# smoothieboard-alt-p5.net
KiCad netlist of a schematic drawn in Altium Designer
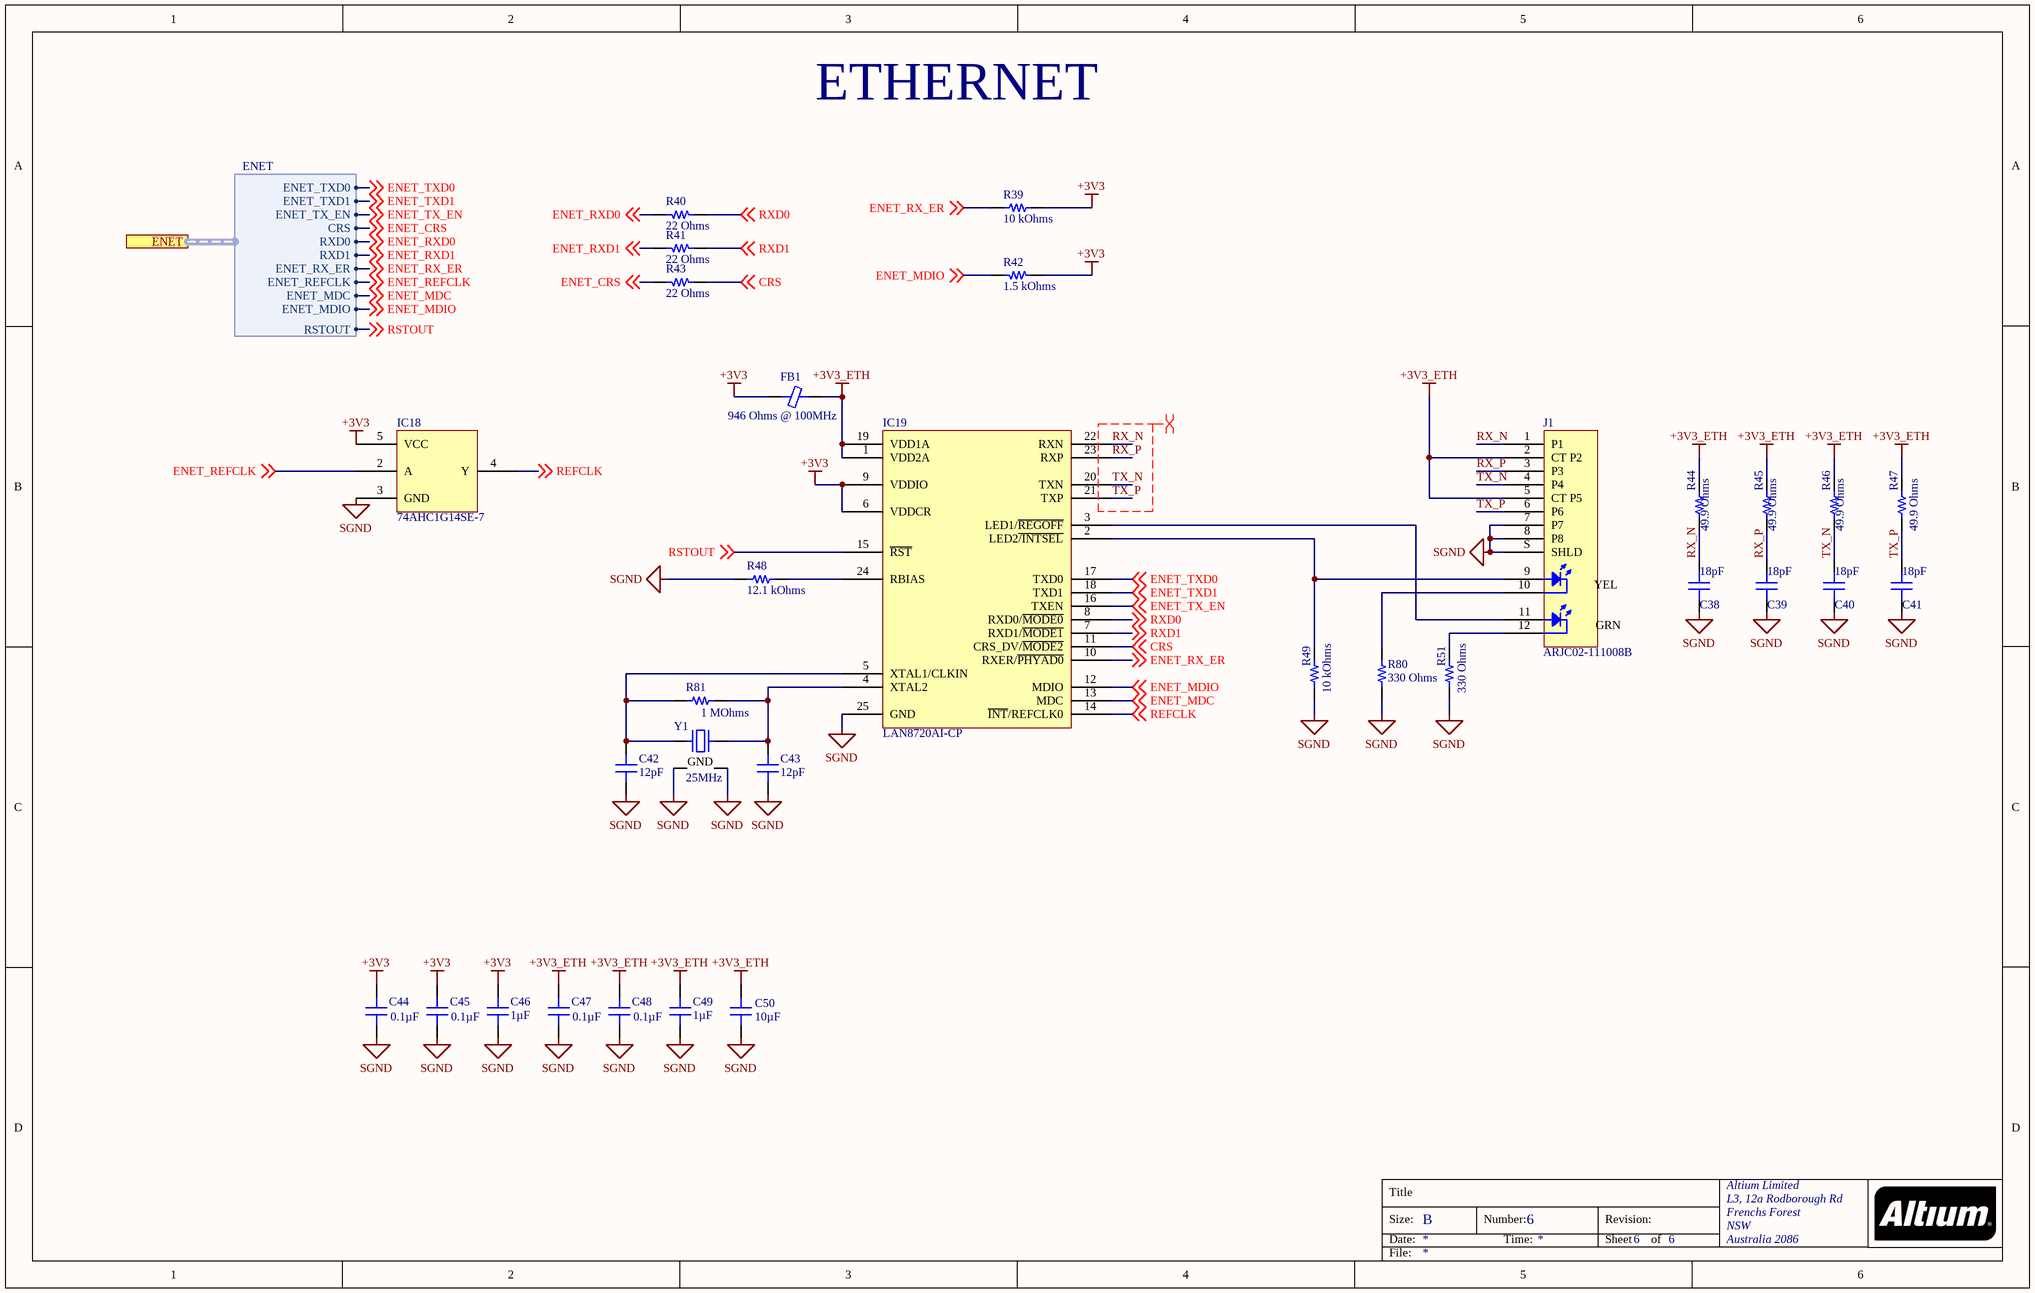
[diagram p0: smoothieboard-alt-p5.SchDoc]

(export (version "E")
  (design (tool "Eeschema 10.0.6"))
  (components
    (comp (ref "C38")
      (value "18pF")
      (footprint "CAP 0402_1005")
      (description "CAP CER 18PF 16V C0G/NP0 0402")
      (fields
        (field (name "PART NUMBER") "VJ0402A180JXJPW1BC")
        (field (name "MANUFACTURER") "Vishay Vitramon")
      )
      (libsource (lib "CAL") (part "Capacitor"))
    )
    (comp (ref "C39")
      (value "18pF")
      (footprint "CAP 0402_1005")
      (description "CAP CER 18PF 16V C0G/NP0 0402")
      (fields
        (field (name "PART NUMBER") "VJ0402A180JXJPW1BC")
        (field (name "MANUFACTURER") "Vishay Vitramon")
      )
      (libsource (lib "CAL") (part "Capacitor"))
    )
    (comp (ref "C40")
      (value "18pF")
      (footprint "CAP 0402_1005")
      (description "CAP CER 18PF 16V C0G/NP0 0402")
      (fields
        (field (name "PART NUMBER") "VJ0402A180JXJPW1BC")
        (field (name "MANUFACTURER") "Vishay Vitramon")
      )
      (libsource (lib "CAL") (part "Capacitor"))
    )
    (comp (ref "C41")
      (value "18pF")
      (footprint "CAP 0402_1005")
      (description "CAP CER 18PF 16V C0G/NP0 0402")
      (fields
        (field (name "PART NUMBER") "VJ0402A180JXJPW1BC")
        (field (name "MANUFACTURER") "Vishay Vitramon")
      )
      (libsource (lib "CAL") (part "Capacitor"))
    )
    (comp (ref "C42")
      (value "12pF")
      (footprint "CAP 0402_1005")
      (description "CAP CER 12PF 10V NP0 0402")
      (fields (field (name "PART NUMBER") "C0402C120J8GAC7867") (field (name "MANUFACTURER") "KEMET"))
      (libsource (lib "CAL") (part "Capacitor"))
    )
    (comp (ref "C43")
      (value "12pF")
      (footprint "CAP 0402_1005")
      (description "CAP CER 12PF 10V NP0 0402")
      (fields (field (name "PART NUMBER") "C0402C120J8GAC7867") (field (name "MANUFACTURER") "KEMET"))
      (libsource (lib "CAL") (part "Capacitor"))
    )
    (comp (ref "C44")
      (value "0.1µF")
      (footprint "CAP 0402_1005")
      (description "CAP CER 0.1UF 6.3V X5R 0402")
      (fields (field (name "PART NUMBER") "CC0402MRX5R5BB104") (field (name "MANUFACTURER") "Yageo"))
      (libsource (lib "CAL") (part "Capacitor"))
    )
    (comp (ref "C45")
      (value "0.1µF")
      (footprint "CAP 0402_1005")
      (description "CAP CER 0.1UF 6.3V X5R 0402")
      (fields (field (name "PART NUMBER") "CC0402MRX5R5BB104") (field (name "MANUFACTURER") "Yageo"))
      (libsource (lib "CAL") (part "Capacitor"))
    )
    (comp (ref "C46")
      (value "1µF")
      (footprint "CAP 0603_1608")
      (description "CAP CER 1UF 50V X5R 0603")
      (fields (field (name "PART NUMBER") "UMK107ABJ105MAHT") (field (name "MANUFACTURER") "Taiyo Yuden"))
      (libsource (lib "CAL") (part "Capacitor"))
    )
    (comp (ref "C47")
      (value "0.1µF")
      (footprint "CAP 0402_1005")
      (description "CAP CER 0.1UF 6.3V X5R 0402")
      (fields (field (name "PART NUMBER") "CC0402MRX5R5BB104") (field (name "MANUFACTURER") "Yageo"))
      (libsource (lib "CAL") (part "Capacitor"))
    )
    (comp (ref "C48")
      (value "0.1µF")
      (footprint "CAP 0402_1005")
      (description "CAP CER 0.1UF 6.3V X5R 0402")
      (fields (field (name "PART NUMBER") "CC0402MRX5R5BB104") (field (name "MANUFACTURER") "Yageo"))
      (libsource (lib "CAL") (part "Capacitor"))
    )
    (comp (ref "C49")
      (value "1µF")
      (footprint "CAP 0603_1608")
      (description "CAP CER 1UF 50V X5R 0603")
      (fields (field (name "PART NUMBER") "UMK107ABJ105MAHT") (field (name "MANUFACTURER") "Taiyo Yuden"))
      (libsource (lib "CAL") (part "Capacitor"))
    )
    (comp (ref "C50")
      (value "10µF")
      (footprint "CAP 0603_1608")
      (description "CAP CER 10UF 6.3V X5R 0603")
      (fields
        (field (name "PART NUMBER") "GRM188R60J106KE47D")
        (field (name "MANUFACTURER") "Murata Electronics")
      )
      (libsource (lib "CAL") (part "Capacitor"))
    )
    (comp (ref "FB1")
      (value "946 Ohms @ 100MHz")
      (footprint "FER 1206_3216")
      (description "FERRITE BEAD 946 OHM 1206 1LN")
      (fields
        (field (name "PART NUMBER") "LF1206E152R-10")
        (field (name "MANUFACTURER") "Laird-Signal Integrity Products")
      )
      (libsource (lib "CAL") (part "Ferrite Chip"))
    )
    (comp (ref "IC18")
      (value "74AHC1G14SE-7")
      (footprint "DIODES INC - SOT353")
      (description "IC INVERTER SCHMITT 1CH SOT353")
      (fields (field (name "MANUFACTURER") "Diodes Incorporated"))
      (libsource (lib "CAL") (part "DIODES 74AHC1G14SE-7"))
    )
    (comp (ref "IC19")
      (value "LAN8720AI-CP")
      (footprint "SMSC QFN-24 4X4MM")
      (description "IC TRANSCEIVER FULL 2/2 24QFN")
      (fields (field (name "MANUFACTURER") "Microchip Technology"))
      (libsource (lib "CAL") (part "SMSC LAN8720"))
    )
    (comp (ref "J1")
      (value "ARJC02-111008B")
      (footprint "ABRACON ARJC02-111008B")
      (description "CONN MAGJACK 1PORT 100 BASE-TX")
      (fields (field (name "MANUFACTURER") "Abracon LLC"))
      (libsource (lib "CAL") (part "Modular Jack with Magnetics Shield LEDS"))
    )
    (comp (ref "R39")
      (value "10 kOhms")
      (footprint "RES 0603_1608")
      (description "RES SMD 10K OHM 5% 1/4W 0603")
      (fields (field (name "PART NUMBER") "RCS060310K0JNEA") (field (name "MANUFACTURER") "Vishay Dale"))
      (libsource (lib "CAL") (part "Resistor"))
    )
    (comp (ref "R40")
      (value "22 Ohms")
      (footprint "RES 0603_1608")
      (description "RES SMD 22 OHM 1% 1/10W 0603")
      (fields
        (field (name "PART NUMBER") "ERJ-3EKF22R0V")
        (field (name "MANUFACTURER") "Panasonic Electronic Components")
      )
      (libsource (lib "CAL") (part "Resistor"))
    )
    (comp (ref "R41")
      (value "22 Ohms")
      (footprint "RES 0603_1608")
      (description "RES SMD 22 OHM 1% 1/10W 0603")
      (fields
        (field (name "PART NUMBER") "ERJ-3EKF22R0V")
        (field (name "MANUFACTURER") "Panasonic Electronic Components")
      )
      (libsource (lib "CAL") (part "Resistor"))
    )
    (comp (ref "R42")
      (value "1.5 kOhms")
      (footprint "RES 0402_1005")
      (description "RES SMD 1.5K OHM 1% 1/5W 0402")
      (fields (field (name "PART NUMBER") "RCS04021K50FKED") (field (name "MANUFACTURER") "Vishay Dale"))
      (libsource (lib "CAL") (part "Resistor"))
    )
    (comp (ref "R43")
      (value "22 Ohms")
      (footprint "RES 0603_1608")
      (description "RES SMD 22 OHM 1% 1/10W 0603")
      (fields
        (field (name "PART NUMBER") "ERJ-3EKF22R0V")
        (field (name "MANUFACTURER") "Panasonic Electronic Components")
      )
      (libsource (lib "CAL") (part "Resistor"))
    )
    (comp (ref "R44")
      (value "49.9 Ohms")
      (footprint "RES 0402_1005")
      (description "RES SMD 49.9 OHM 0.5% 1/16W 0402")
      (fields (field (name "PART NUMBER") "RR0510R-49R9-D") (field (name "MANUFACTURER") "Susumu"))
      (libsource (lib "CAL") (part "Resistor"))
    )
    (comp (ref "R45")
      (value "49.9 Ohms")
      (footprint "RES 0402_1005")
      (description "RES SMD 49.9 OHM 0.5% 1/16W 0402")
      (fields (field (name "PART NUMBER") "RR0510R-49R9-D") (field (name "MANUFACTURER") "Susumu"))
      (libsource (lib "CAL") (part "Resistor"))
    )
    (comp (ref "R46")
      (value "49.9 Ohms")
      (footprint "RES 0402_1005")
      (description "RES SMD 49.9 OHM 0.5% 1/16W 0402")
      (fields (field (name "PART NUMBER") "RR0510R-49R9-D") (field (name "MANUFACTURER") "Susumu"))
      (libsource (lib "CAL") (part "Resistor"))
    )
    (comp (ref "R47")
      (value "49.9 Ohms")
      (footprint "RES 0402_1005")
      (description "RES SMD 49.9 OHM 0.5% 1/16W 0402")
      (fields (field (name "PART NUMBER") "RR0510R-49R9-D") (field (name "MANUFACTURER") "Susumu"))
      (libsource (lib "CAL") (part "Resistor"))
    )
    (comp (ref "R48")
      (value "12.1 kOhms")
      (footprint "RES 0402_1005")
      (description "RES SMD 12.1K OHM 1% 1/16W 0402")
      (fields (field (name "PART NUMBER") "CRCW040212K1FKTD") (field (name "MANUFACTURER") "Vishay Dale"))
      (libsource (lib "CAL") (part "Resistor"))
    )
    (comp (ref "R49")
      (value "10 kOhms")
      (footprint "RES 0603_1608")
      (description "RES SMD 10K OHM 5% 1/4W 0603")
      (fields (field (name "PART NUMBER") "RCS060310K0JNEA") (field (name "MANUFACTURER") "Vishay Dale"))
      (libsource (lib "CAL") (part "Resistor"))
    )
    (comp (ref "R51")
      (value "330 Ohms")
      (footprint "RES 0603_1608")
      (description "RES SMD 330 OHM 5% 1/10W 0603")
      (fields
        (field (name "PART NUMBER") "ERJ-3GEYJ331V")
        (field (name "MANUFACTURER") "Panasonic Electronic Components")
      )
      (libsource (lib "CAL") (part "Resistor"))
    )
    (comp (ref "R80")
      (value "330 Ohms")
      (footprint "RES 0603_1608")
      (description "RES SMD 330 OHM 5% 1/10W 0603")
      (fields
        (field (name "PART NUMBER") "ERJ-3GEYJ331V")
        (field (name "MANUFACTURER") "Panasonic Electronic Components")
      )
      (libsource (lib "CAL") (part "Resistor"))
    )
    (comp (ref "R81")
      (value "1 MOhms")
      (footprint "RES 0402_1005")
      (description "RES SMD 1M OHM 1% 1/5W 0402")
      (fields (field (name "PART NUMBER") "RCS04021M00FKED") (field (name "MANUFACTURER") "Vishay Dale"))
      (libsource (lib "CAL") (part "Resistor"))
    )
    (comp (ref "Y1")
      (value "25MHz")
      (footprint "KYOCERA CX2016DB")
      (description "CRYSTAL 25.0000MHZ 12PF SMD")
      (fields
        (field (name "PART NUMBER") "CX2016DB25000H0FLJC1")
        (field (name "MANUFACTURER") "Kyocera International Inc. Electronic Components")
      )
      (libsource (lib "CAL") (part "Kyocera Crystal CX2016DB"))
    )
  )
  (nets
    (net (code "2") (name "+3V3") (class "Default")
      (node (ref "C44") (pin "2") (pinfunction "2_2") (pintype "passive"))
      (node (ref "C45") (pin "2") (pinfunction "2_2") (pintype "passive"))
      (node (ref "C46") (pin "2") (pinfunction "2_2") (pintype "passive"))
      (node (ref "FB1") (pin "1") (pinfunction "1_1") (pintype "passive"))
      (node (ref "IC18") (pin "5") (pinfunction "VCC_5") (pintype "passive"))
      (node (ref "IC19") (pin "6") (pinfunction "VDDCR_6") (pintype "passive"))
      (node (ref "IC19") (pin "9") (pinfunction "VDDIO_9") (pintype "passive"))
      (node (ref "R39") (pin "2") (pinfunction "2_2") (pintype "passive"))
      (node (ref "R42") (pin "1") (pinfunction "1_1") (pintype "passive"))
    )
    (net (code "3") (name "+3V3_ETH") (class "Default")
      (node (ref "C47") (pin "2") (pinfunction "2_2") (pintype "passive"))
      (node (ref "C48") (pin "2") (pinfunction "2_2") (pintype "passive"))
      (node (ref "C49") (pin "2") (pinfunction "2_2") (pintype "passive"))
      (node (ref "C50") (pin "2") (pinfunction "2_2") (pintype "passive"))
      (node (ref "FB1") (pin "2") (pinfunction "2_2") (pintype "passive"))
      (node (ref "IC19") (pin "1") (pinfunction "VDD2A_1") (pintype "passive"))
      (node (ref "IC19") (pin "19") (pinfunction "VDD1A_19") (pintype "passive"))
      (node (ref "J1") (pin "2") (pinfunction "CT_P2_2") (pintype "passive"))
      (node (ref "J1") (pin "5") (pinfunction "CT_P5_5") (pintype "passive"))
      (node (ref "R44") (pin "2") (pinfunction "2_2") (pintype "passive"))
      (node (ref "R45") (pin "2") (pinfunction "2_2") (pintype "passive"))
      (node (ref "R46") (pin "2") (pinfunction "2_2") (pintype "passive"))
      (node (ref "R47") (pin "2") (pinfunction "2_2") (pintype "passive"))
    )
    (net (code "4") (name "/RX_N") (class "Default")
      (node (ref "C38") (pin "2") (pinfunction "2_2") (pintype "passive"))
      (node (ref "IC19") (pin "22") (pinfunction "RXN_22") (pintype "passive"))
      (node (ref "J1") (pin "1") (pinfunction "P1_1") (pintype "passive"))
      (node (ref "R44") (pin "1") (pinfunction "1_1") (pintype "passive"))
    )
    (net (code "5") (name "/RX_P") (class "Default")
      (node (ref "C39") (pin "2") (pinfunction "2_2") (pintype "passive"))
      (node (ref "IC19") (pin "23") (pinfunction "RXP_23") (pintype "passive"))
      (node (ref "J1") (pin "3") (pinfunction "P3_3") (pintype "passive"))
      (node (ref "R45") (pin "1") (pinfunction "1_1") (pintype "passive"))
    )
    (net (code "6") (name "/TX_N") (class "Default")
      (node (ref "C40") (pin "2") (pinfunction "2_2") (pintype "passive"))
      (node (ref "IC19") (pin "20") (pinfunction "TXN_20") (pintype "passive"))
      (node (ref "J1") (pin "4") (pinfunction "P4_4") (pintype "passive"))
      (node (ref "R46") (pin "1") (pinfunction "1_1") (pintype "passive"))
    )
    (net (code "7") (name "/TX_P") (class "Default")
      (node (ref "C41") (pin "2") (pinfunction "2_2") (pintype "passive"))
      (node (ref "IC19") (pin "21") (pinfunction "TXP_21") (pintype "passive"))
      (node (ref "J1") (pin "6") (pinfunction "P6_6") (pintype "passive"))
      (node (ref "R47") (pin "1") (pinfunction "1_1") (pintype "passive"))
    )
    (net (code "9") (name "CRS") (class "Default")
      (node (ref "IC19") (pin "11") (pinfunction "CRS_DV/~{MODE2}_11") (pintype "passive"))
      (node (ref "R43") (pin "1") (pinfunction "1_1") (pintype "passive"))
    )
    (net (code "10") (name "ENET_CRS") (class "Default")
      (node (ref "R43") (pin "2") (pinfunction "2_2") (pintype "passive"))
    )
    (net (code "11") (name "ENET_MDC") (class "Default")
      (node (ref "IC19") (pin "13") (pinfunction "MDC_13") (pintype "passive"))
    )
    (net (code "12") (name "ENET_MDIO") (class "Default")
      (node (ref "IC19") (pin "12") (pinfunction "MDIO_12") (pintype "passive"))
      (node (ref "R42") (pin "2") (pinfunction "2_2") (pintype "passive"))
    )
    (net (code "13") (name "ENET_REFCLK") (class "Default")
      (node (ref "IC18") (pin "2") (pinfunction "A_2") (pintype "passive"))
    )
    (net (code "14") (name "ENET_RXD0") (class "Default")
      (node (ref "R40") (pin "2") (pinfunction "2_2") (pintype "passive"))
    )
    (net (code "15") (name "ENET_RXD1") (class "Default")
      (node (ref "R41") (pin "2") (pinfunction "2_2") (pintype "passive"))
    )
    (net (code "16") (name "ENET_RX_ER") (class "Default")
      (node (ref "IC19") (pin "10") (pinfunction "RXER/~{PHYAD0}_10") (pintype "passive"))
      (node (ref "R39") (pin "1") (pinfunction "1_1") (pintype "passive"))
    )
    (net (code "17") (name "ENET_TXD0") (class "Default")
      (node (ref "IC19") (pin "17") (pinfunction "TXD0_17") (pintype "passive"))
    )
    (net (code "18") (name "ENET_TXD1") (class "Default")
      (node (ref "IC19") (pin "18") (pinfunction "TXD1_18") (pintype "passive"))
    )
    (net (code "19") (name "ENET_TX_EN") (class "Default")
      (node (ref "IC19") (pin "16") (pinfunction "TXEN_16") (pintype "passive"))
    )
    (net (code "20") (name "Net-(IC19-LED1{slash}~{REGOFF})") (class "Default")
      (node (ref "IC19") (pin "3") (pinfunction "LED1/~{REGOFF}_3") (pintype "passive"))
      (node (ref "J1") (pin "11") (pinfunction "P11_11") (pintype "passive"))
    )
    (net (code "21") (name "Net-(IC19-LED2~{{slash}INTSEL})") (class "Default")
      (node (ref "IC19") (pin "2") (pinfunction "LED2~{/INTSEL}_2") (pintype "passive"))
      (node (ref "J1") (pin "9") (pinfunction "P9_9") (pintype "passive"))
      (node (ref "R49") (pin "1") (pinfunction "1_1") (pintype "passive"))
    )
    (net (code "22") (name "Net-(IC19-RBIAS)") (class "Default")
      (node (ref "IC19") (pin "24") (pinfunction "RBIAS_24") (pintype "passive"))
      (node (ref "R48") (pin "2") (pinfunction "2_2") (pintype "passive"))
    )
    (net (code "23") (name "Net-(IC19-XTAL1{slash}CLKIN)") (class "Default")
      (node (ref "C42") (pin "1") (pinfunction "1_1") (pintype "passive"))
      (node (ref "IC19") (pin "5") (pinfunction "XTAL1/CLKIN_5") (pintype "passive"))
      (node (ref "R81") (pin "2") (pinfunction "2_2") (pintype "passive"))
      (node (ref "Y1") (pin "1") (pinfunction "1_1") (pintype "passive"))
    )
    (net (code "24") (name "Net-(IC19-XTAL2)") (class "Default")
      (node (ref "C43") (pin "1") (pinfunction "1_1") (pintype "passive"))
      (node (ref "IC19") (pin "4") (pinfunction "XTAL2_4") (pintype "passive"))
      (node (ref "R81") (pin "1") (pinfunction "1_1") (pintype "passive"))
      (node (ref "Y1") (pin "3") (pinfunction "3_3") (pintype "passive"))
    )
    (net (code "25") (name "Net-(J1-P10)") (class "Default")
      (node (ref "J1") (pin "10") (pinfunction "P10_10") (pintype "passive"))
      (node (ref "R80") (pin "1") (pinfunction "1_1") (pintype "passive"))
    )
    (net (code "26") (name "Net-(J1-P12)") (class "Default")
      (node (ref "J1") (pin "12") (pinfunction "P12_12") (pintype "passive"))
      (node (ref "R51") (pin "1") (pinfunction "1_1") (pintype "passive"))
    )
    (net (code "27") (name "REFCLK") (class "Default")
      (node (ref "IC18") (pin "4") (pinfunction "Y_4") (pintype "passive"))
      (node (ref "IC19") (pin "14") (pinfunction "~{INT}/REFCLK0_14") (pintype "passive"))
    )
    (net (code "28") (name "RSTOUT") (class "Default")
      (node (ref "IC19") (pin "15") (pinfunction "~{RST}_15") (pintype "passive"))
    )
    (net (code "29") (name "RXD0") (class "Default")
      (node (ref "IC19") (pin "8") (pinfunction "RXD0/~{MODE0}_8") (pintype "passive"))
      (node (ref "R40") (pin "1") (pinfunction "1_1") (pintype "passive"))
    )
    (net (code "30") (name "RXD1") (class "Default")
      (node (ref "IC19") (pin "7") (pinfunction "RXD1/~{MODE1}_7") (pintype "passive"))
      (node (ref "R41") (pin "1") (pinfunction "1_1") (pintype "passive"))
    )
    (net (code "31") (name "SGND") (class "Default")
      (node (ref "C38") (pin "1") (pinfunction "1_1") (pintype "passive"))
      (node (ref "C39") (pin "1") (pinfunction "1_1") (pintype "passive"))
      (node (ref "C40") (pin "1") (pinfunction "1_1") (pintype "passive"))
      (node (ref "C41") (pin "1") (pinfunction "1_1") (pintype "passive"))
      (node (ref "C42") (pin "2") (pinfunction "2_2") (pintype "passive"))
      (node (ref "C43") (pin "2") (pinfunction "2_2") (pintype "passive"))
      (node (ref "C44") (pin "1") (pinfunction "1_1") (pintype "passive"))
      (node (ref "C45") (pin "1") (pinfunction "1_1") (pintype "passive"))
      (node (ref "C46") (pin "1") (pinfunction "1_1") (pintype "passive"))
      (node (ref "C47") (pin "1") (pinfunction "1_1") (pintype "passive"))
      (node (ref "C48") (pin "1") (pinfunction "1_1") (pintype "passive"))
      (node (ref "C49") (pin "1") (pinfunction "1_1") (pintype "passive"))
      (node (ref "C50") (pin "1") (pinfunction "1_1") (pintype "passive"))
      (node (ref "IC18") (pin "3") (pinfunction "GND_3") (pintype "passive"))
      (node (ref "IC19") (pin "25") (pinfunction "GND_25") (pintype "passive"))
      (node (ref "J1") (pin "7") (pinfunction "P7_7") (pintype "passive"))
      (node (ref "J1") (pin "8") (pinfunction "P8_8") (pintype "passive"))
      (node (ref "J1") (pin "S") (pinfunction "SHLD_S") (pintype "passive"))
      (node (ref "R48") (pin "1") (pinfunction "1_1") (pintype "passive"))
      (node (ref "R49") (pin "2") (pinfunction "2_2") (pintype "passive"))
      (node (ref "R51") (pin "2") (pinfunction "2_2") (pintype "passive"))
      (node (ref "R80") (pin "2") (pinfunction "2_2") (pintype "passive"))
      (node (ref "Y1") (pin "2") (pinfunction "GND_2") (pintype "passive"))
      (node (ref "Y1") (pin "4") (pinfunction "GND_4") (pintype "passive"))
    )
  )
)
